# H01R0_Backend.net
KiCad netlist of a schematic drawn in Altium Designer
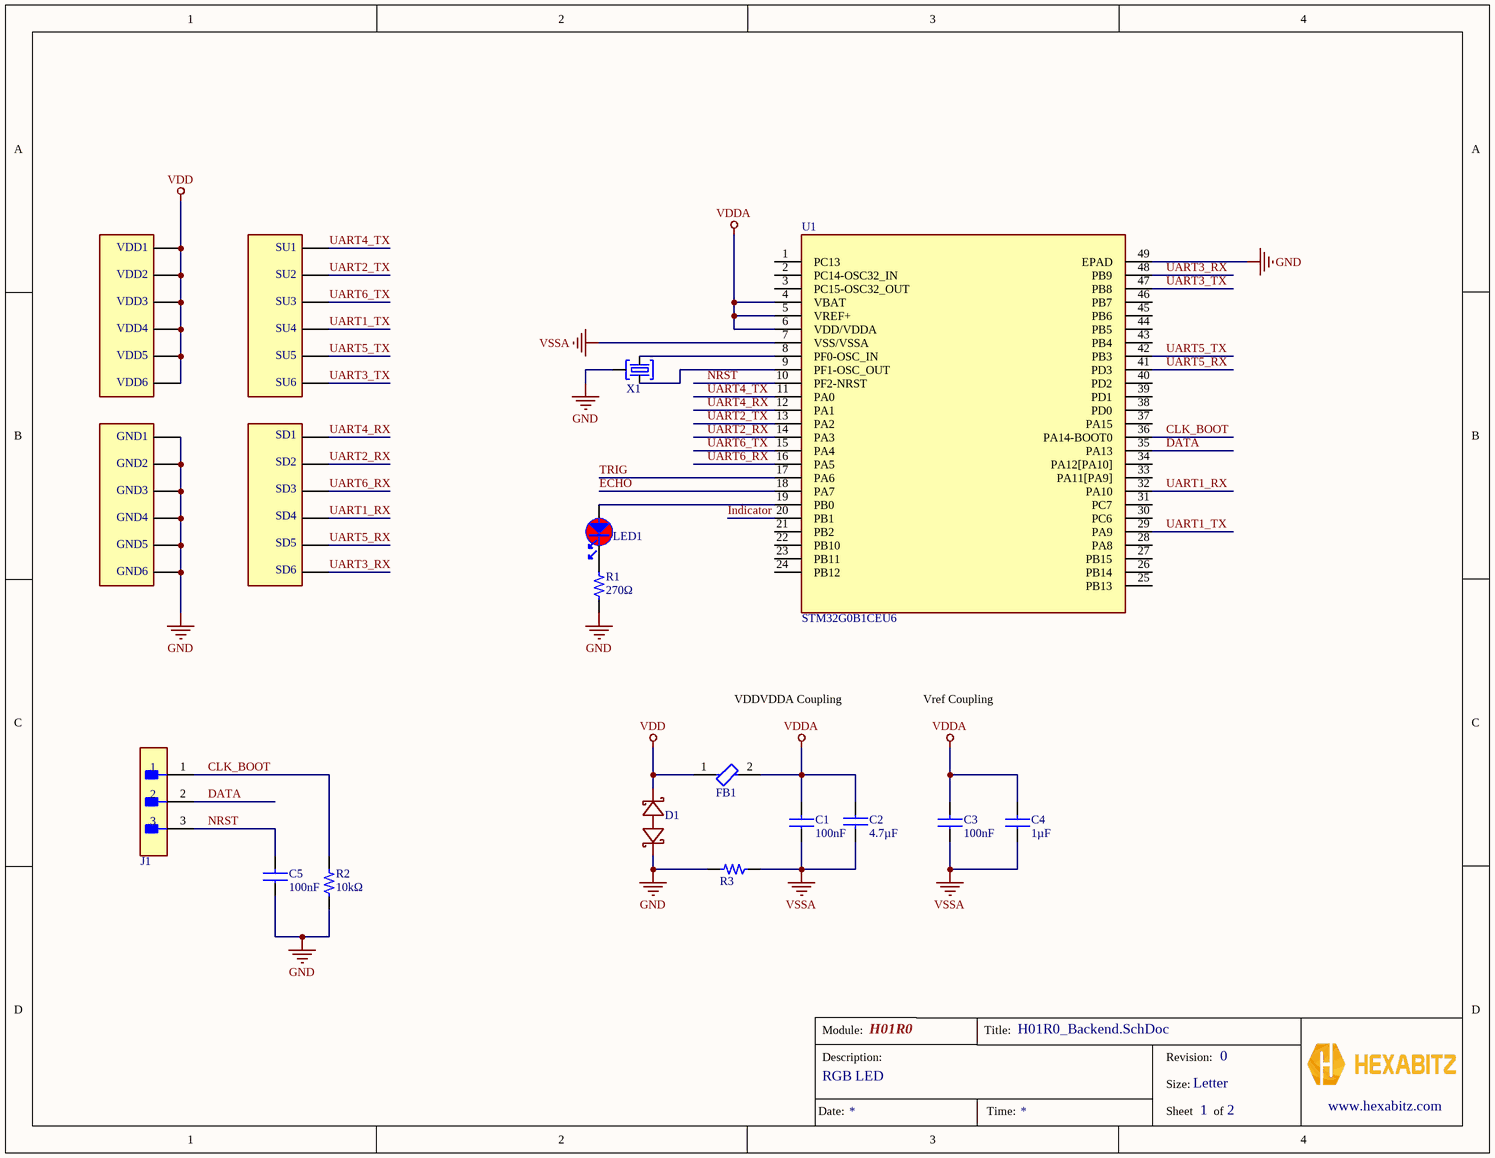
[diagram p0: H01R0_Backend.SchDoc]

(export (version "E")
  (design (tool "Eeschema 10.0.6"))
  (components
    (comp (ref "C1")
      (value "100nF")
      (footprint "C0603")
      (fields
        (field (name "MANUFACTURER") "Samsung Electro-Mechanics")
        (field (name "MANUFACTURER PART NUMBER") "CL10B104KA8NNNC")
        (field (name "TOLERANCE") "10%")
      )
      (libsource (lib "Hexabitz Altium Library") (part "generic Capacitor"))
    )
    (comp (ref "C2")
      (value "4.7µF")
      (footprint "C0805")
      (fields
        (field (name "MANUFACTURER") "Samsung Electro-Mechanics")
        (field (name "MANUFACTURER PART NUMBER") "CL21X475KAQNNNE")
        (field (name "TOLERANCE") "10%")
      )
      (libsource (lib "Hexabitz Altium Library") (part "generic Capacitor"))
    )
    (comp (ref "C3")
      (value "100nF")
      (footprint "C0603")
      (fields
        (field (name "MANUFACTURER") "Samsung Electro-Mechanics")
        (field (name "MANUFACTURER PART NUMBER") "CL10B104KA8NNNC")
        (field (name "TOLERANCE") "10%")
      )
      (libsource (lib "Hexabitz Altium Library") (part "generic Capacitor"))
    )
    (comp (ref "C4")
      (value "1µF")
      (footprint "C0805")
      (description "Ceramic Capacitor, Ceramic, 16V, 10% +Tol, 10% -Tol, X7R, 15% TC, 1uF, Surface Mount, 0805")
      (fields
        (field (name "MANUFACTURER") "Yageo Group")
        (field (name "MANUFACTURER PART NUMBER") "CC0805KKX7R7BB105")
      )
      (libsource (lib "Hexabitz Altium Library") (part "generic Capacitor"))
    )
    (comp (ref "C5")
      (value "100nF")
      (footprint "C0603")
      (fields
        (field (name "MANUFACTURER") "Samsung Electro-Mechanics")
        (field (name "MANUFACTURER PART NUMBER") "CL10B104KA8NNNC")
        (field (name "TOLERANCE") "10%")
      )
      (libsource (lib "Hexabitz Altium Library") (part "generic Capacitor"))
    )
    (comp (ref "D1")
      (value "CDSOD323-T03SC")
      (footprint "SOD2513X114N")
      (description "A 3V, 350W, bi-directional, standard capacitance, SOD323 pkg TVS Diode ¦ Bourns CDSOD323-T03SC")
      (fields (field (name "MANUFACTURER") "Bourns"))
      (libsource (lib "Hexabitz Altium Library") (part "CDSOD323-T03SC"))
    )
    (comp (ref "FB1")
      (value "MMZ1608Y300B")
      (footprint "FP-MMZ1608-0_8-MFG")
      (description "Ferrite Beads 0603 30ohms 1500mA Signal Line AEC-Q200")
      (fields
        (field (name "MANUFACTURER") "TDK")
        (field (name "MANUFACTURER PART NUMBER") "MMZ1608Y300BTD25")
      )
      (libsource (lib "Hexabitz Altium Library") (part "MMZ1608Y300B"))
    )
    (comp (ref "GND1")
      (value "HEXABIT_UART_PORT")
      (footprint "HEXABIT_POWER_PORT_D")
      (libsource (lib "hexabitz_connectors.Library") (part "HEXABIT_POWER_PORT_D"))
    )
    (comp (ref "GND2")
      (value "HEXABIT_UART_PORT")
      (footprint "HEXABIT_POWER_PORT_D")
      (libsource (lib "hexabitz_connectors.Library") (part "HEXABIT_POWER_PORT_D"))
    )
    (comp (ref "GND3")
      (value "HEXABIT_UART_PORT")
      (footprint "HEXABIT_POWER_PORT_D")
      (libsource (lib "hexabitz_connectors.Library") (part "HEXABIT_POWER_PORT_D"))
    )
    (comp (ref "GND4")
      (value "HEXABIT_UART_PORT")
      (footprint "HEXABIT_POWER_PORT_D")
      (libsource (lib "hexabitz_connectors.Library") (part "HEXABIT_POWER_PORT_D"))
    )
    (comp (ref "GND5")
      (value "HEXABIT_UART_PORT")
      (footprint "HEXABIT_POWER_PORT_D")
      (libsource (lib "hexabitz_connectors.Library") (part "HEXABIT_POWER_PORT_D"))
    )
    (comp (ref "GND6")
      (value "HEXABIT_UART_PORT")
      (footprint "HEXABIT_POWER_PORT_D")
      (libsource (lib "hexabitz_connectors.Library") (part "HEXABIT_POWER_PORT_D"))
    )
    (comp (ref "J1")
      (value "TSW-103-14-G-S")
      (footprint "FP-TSW-103-14-G-S-MFG")
      (description "CONN HEADER VERT 3POS 2.54MM")
      (libsource (lib "Altium Content Vault") (part "cd3439d6ef35ae5d9b27ec4fdd3e828"))
    )
    (comp (ref "LED1")
      (value "VLMS1300-GS08")
      (footprint "FP-6_541-5092_01-4-MFG")
      (description "LED Uni-Color Super Red 639nm 2-Pin Chip 0603(1608Metric) T/R")
      (fields (field (name "MANUFACTURER") "Vishay Semiconductors"))
      (libsource (lib "Hexabitz Altium Library") (part "VLMS1300-GS08"))
    )
    (comp (ref "R1")
      (value "270Ω")
      (footprint "R0603")
      (description "Res Thick Film 0603 270 Ohm 5% 0.1W(1/10W) ±200ppm/C Pad SMD Automotive T/R")
      (fields
        (field (name "MANUFACTURER") "Panasonic")
        (field (name "MANUFACTURER PART NUMBER") "ERJ-3GEYJ271V")
      )
      (libsource (lib "") (part "generic Resistor_2"))
    )
    (comp (ref "R2")
      (value "10kΩ")
      (footprint "R0603")
      (description "100mW Thick Film Resistors ±100ppm/℃ ±1% 10kΩ 0603 Chip Resistor - Surface Mount ROHS")
      (fields
        (field (name "MANUFACTURER") "Yageo Group")
        (field (name "MANUFACTURER PART NUMBER") "RC0603FR-0710KL")
      )
      (libsource (lib "") (part "generic Resistor_1"))
    )
    (comp (ref "R3")
      (value "Manufacturer Part Number")
      (footprint "R0603")
      (libsource (lib "Hexabitz Altium Library") (part "generic Resistor"))
    )
    (comp (ref "SD1")
      (value "HEXABIT_UART_PORT")
      (footprint "HEXABIT_UART_PORT_D")
      (libsource (lib "hexabitz_connectors.Library") (part "HEXABIT_UART_PORT_D"))
    )
    (comp (ref "SD2")
      (value "HEXABIT_UART_PORT")
      (footprint "HEXABIT_UART_PORT_D")
      (libsource (lib "hexabitz_connectors.Library") (part "HEXABIT_UART_PORT_D"))
    )
    (comp (ref "SD3")
      (value "HEXABIT_UART_PORT")
      (footprint "HEXABIT_UART_PORT_D")
      (libsource (lib "hexabitz_connectors.Library") (part "HEXABIT_UART_PORT_D"))
    )
    (comp (ref "SD4")
      (value "HEXABIT_UART_PORT")
      (footprint "HEXABIT_UART_PORT_D")
      (libsource (lib "hexabitz_connectors.Library") (part "HEXABIT_UART_PORT_D"))
    )
    (comp (ref "SD5")
      (value "HEXABIT_UART_PORT")
      (footprint "HEXABIT_UART_PORT_D")
      (libsource (lib "hexabitz_connectors.Library") (part "HEXABIT_UART_PORT_D"))
    )
    (comp (ref "SD6")
      (value "HEXABIT_UART_PORT")
      (footprint "HEXABIT_UART_PORT_D")
      (libsource (lib "hexabitz_connectors.Library") (part "HEXABIT_UART_PORT_D"))
    )
    (comp (ref "SU1")
      (value "HEXABIT_UART_PORT")
      (footprint "HEXABIT_UART_PORT_U")
      (libsource (lib "hexabitz_connectors.Library") (part "HEXABIT_UART_PORT_U"))
    )
    (comp (ref "SU2")
      (value "HEXABIT_UART_PORT")
      (footprint "HEXABIT_UART_PORT_U")
      (libsource (lib "hexabitz_connectors.Library") (part "HEXABIT_UART_PORT_U"))
    )
    (comp (ref "SU3")
      (value "HEXABIT_UART_PORT")
      (footprint "HEXABIT_UART_PORT_U")
      (libsource (lib "hexabitz_connectors.Library") (part "HEXABIT_UART_PORT_U"))
    )
    (comp (ref "SU4")
      (value "HEXABIT_UART_PORT")
      (footprint "HEXABIT_UART_PORT_U")
      (libsource (lib "hexabitz_connectors.Library") (part "HEXABIT_UART_PORT_U"))
    )
    (comp (ref "SU5")
      (value "HEXABIT_UART_PORT")
      (footprint "HEXABIT_UART_PORT_U")
      (libsource (lib "hexabitz_connectors.Library") (part "HEXABIT_UART_PORT_U"))
    )
    (comp (ref "SU6")
      (value "HEXABIT_UART_PORT")
      (footprint "HEXABIT_UART_PORT_U")
      (libsource (lib "hexabitz_connectors.Library") (part "HEXABIT_UART_PORT_U"))
    )
    (comp (ref "U1")
      (value "STM32G0B1CEU6")
      (footprint "QFN50P700X700X65-49N-D")
      (description "MCU 32-bit ARM Cortex M0+ RISC 512KB Flash 1.8V/2.5V/3.3V 48-Pin UFQFPN EP Tray")
      (fields
        (field (name "MANUFACTURER") "STMicroelectronics")
        (field (name "MANUFACTURER PART NUMBER") "STM32G0B1CEU6")
      )
      (libsource (lib "Hexabitz Altium Library") (part "STM32G0B1CEU6"))
    )
    (comp (ref "VDD1")
      (value "HEXABIT_UART_PORT")
      (footprint "HEXABIT_POWER_PORT_U")
      (libsource (lib "hexabitz_connectors.Library") (part "HEXABIT_POWER_PORT_U"))
    )
    (comp (ref "VDD2")
      (value "HEXABIT_UART_PORT")
      (footprint "HEXABIT_POWER_PORT_U")
      (libsource (lib "hexabitz_connectors.Library") (part "HEXABIT_POWER_PORT_U"))
    )
    (comp (ref "VDD3")
      (value "HEXABIT_UART_PORT")
      (footprint "HEXABIT_POWER_PORT_U")
      (libsource (lib "hexabitz_connectors.Library") (part "HEXABIT_POWER_PORT_U"))
    )
    (comp (ref "VDD4")
      (value "HEXABIT_UART_PORT")
      (footprint "HEXABIT_POWER_PORT_U")
      (libsource (lib "hexabitz_connectors.Library") (part "HEXABIT_POWER_PORT_U"))
    )
    (comp (ref "VDD5")
      (value "HEXABIT_UART_PORT")
      (footprint "HEXABIT_POWER_PORT_U")
      (libsource (lib "hexabitz_connectors.Library") (part "HEXABIT_POWER_PORT_U"))
    )
    (comp (ref "VDD6")
      (value "HEXABIT_UART_PORT")
      (footprint "HEXABIT_POWER_PORT_U")
      (libsource (lib "hexabitz_connectors.Library") (part "HEXABIT_POWER_PORT_U"))
    )
    (comp (ref "X1")
      (value "CSTCE8M00G52Z-R0")
      (footprint "XTALL_CSTCE8M00G52")
      (description "Ceramic Resonator 8MHz ±0.5% (Tol) ±0.2% (Stability) 10pF 40Ohm 3-Pin CSMD T/R")
      (fields (field (name "MANUFACTURER") "Murata") (field (name "TOLERANCE") "0.5%"))
      (libsource (lib "Hexabitz Altium Library") (part "CSTCE8M00G52Z-R0"))
    )
  )
  (nets
    (net (code "1") (name "/CLK_BOOT") (class "Default")
      (node (ref "J1") (pin "1") (pinfunction "1_1") (pintype "passive"))
      (node (ref "R2") (pin "1") (pinfunction "1_1") (pintype "passive"))
      (node (ref "U1") (pin "36") (pinfunction "PA14-BOOT0_36") (pintype "passive"))
    )
    (net (code "2") (name "/DATA") (class "Default")
      (node (ref "J1") (pin "2") (pinfunction "2_2") (pintype "passive"))
      (node (ref "U1") (pin "35") (pinfunction "PA13_35") (pintype "passive"))
    )
    (net (code "3") (name "/ECHO") (class "Default")
      (node (ref "U1") (pin "18") (pinfunction "PA7_18") (pintype "passive"))
    )
    (net (code "4") (name "/Indicator") (class "Default")
      (node (ref "U1") (pin "20") (pinfunction "PB1_20") (pintype "passive"))
    )
    (net (code "5") (name "/NRST") (class "Default")
      (node (ref "C5") (pin "2") (pinfunction "2_2") (pintype "passive"))
      (node (ref "J1") (pin "3") (pinfunction "3_3") (pintype "passive"))
      (node (ref "U1") (pin "10") (pinfunction "PF2-NRST_10") (pintype "passive"))
    )
    (net (code "6") (name "/TRIG") (class "Default")
      (node (ref "U1") (pin "17") (pinfunction "PA6_17") (pintype "passive"))
    )
    (net (code "7") (name "/UART1_RX") (class "Default")
      (node (ref "SD4") (pin "UART_D") (pinfunction "UART_D_UART_D") (pintype "passive"))
      (node (ref "U1") (pin "32") (pinfunction "PA10_32") (pintype "passive"))
    )
    (net (code "8") (name "/UART1_TX") (class "Default")
      (node (ref "SU4") (pin "UART_U") (pinfunction "UART_U_UART_U") (pintype "passive"))
      (node (ref "U1") (pin "29") (pinfunction "PA9_29") (pintype "passive"))
    )
    (net (code "9") (name "/UART2_RX") (class "Default")
      (node (ref "SD2") (pin "UART_D") (pinfunction "UART_D_UART_D") (pintype "passive"))
      (node (ref "U1") (pin "14") (pinfunction "PA3_14") (pintype "passive"))
    )
    (net (code "10") (name "/UART2_TX") (class "Default")
      (node (ref "SU2") (pin "UART_U") (pinfunction "UART_U_UART_U") (pintype "passive"))
      (node (ref "U1") (pin "13") (pinfunction "PA2_13") (pintype "passive"))
    )
    (net (code "11") (name "/UART3_RX") (class "Default")
      (node (ref "SD6") (pin "UART_D") (pinfunction "UART_D_UART_D") (pintype "passive"))
      (node (ref "U1") (pin "48") (pinfunction "PB9_48") (pintype "passive"))
    )
    (net (code "12") (name "/UART3_TX") (class "Default")
      (node (ref "SU6") (pin "UART_U") (pinfunction "UART_U_UART_U") (pintype "passive"))
      (node (ref "U1") (pin "47") (pinfunction "PB8_47") (pintype "passive"))
    )
    (net (code "13") (name "/UART4_RX") (class "Default")
      (node (ref "SD1") (pin "UART_D") (pinfunction "UART_D_UART_D") (pintype "passive"))
      (node (ref "U1") (pin "12") (pinfunction "PA1_12") (pintype "passive"))
    )
    (net (code "14") (name "/UART4_TX") (class "Default")
      (node (ref "SU1") (pin "UART_U") (pinfunction "UART_U_UART_U") (pintype "passive"))
      (node (ref "U1") (pin "11") (pinfunction "PA0_11") (pintype "passive"))
    )
    (net (code "15") (name "/UART5_RX") (class "Default")
      (node (ref "SD5") (pin "UART_D") (pinfunction "UART_D_UART_D") (pintype "passive"))
      (node (ref "U1") (pin "41") (pinfunction "PD3_41") (pintype "passive"))
    )
    (net (code "16") (name "/UART5_TX") (class "Default")
      (node (ref "SU5") (pin "UART_U") (pinfunction "UART_U_UART_U") (pintype "passive"))
      (node (ref "U1") (pin "42") (pinfunction "PB3_42") (pintype "passive"))
    )
    (net (code "17") (name "/UART6_RX") (class "Default")
      (node (ref "SD3") (pin "UART_D") (pinfunction "UART_D_UART_D") (pintype "passive"))
      (node (ref "U1") (pin "16") (pinfunction "PA5_16") (pintype "passive"))
    )
    (net (code "18") (name "/UART6_TX") (class "Default")
      (node (ref "SU3") (pin "UART_U") (pinfunction "UART_U_UART_U") (pintype "passive"))
      (node (ref "U1") (pin "15") (pinfunction "PA4_15") (pintype "passive"))
    )
    (net (code "19") (name "GND") (class "Default")
      (node (ref "C5") (pin "1") (pinfunction "1_1") (pintype "passive"))
      (node (ref "D1") (pin "1") (pinfunction "A_1") (pintype "passive"))
      (node (ref "GND1") (pin "Pwr_D") (pinfunction "Pwr_D_Pwr_D") (pintype "passive"))
      (node (ref "GND2") (pin "Pwr_D") (pinfunction "Pwr_D_Pwr_D") (pintype "passive"))
      (node (ref "GND3") (pin "Pwr_D") (pinfunction "Pwr_D_Pwr_D") (pintype "passive"))
      (node (ref "GND4") (pin "Pwr_D") (pinfunction "Pwr_D_Pwr_D") (pintype "passive"))
      (node (ref "GND5") (pin "Pwr_D") (pinfunction "Pwr_D_Pwr_D") (pintype "passive"))
      (node (ref "GND6") (pin "Pwr_D") (pinfunction "Pwr_D_Pwr_D") (pintype "passive"))
      (node (ref "R1") (pin "1") (pinfunction "1_1") (pintype "passive"))
      (node (ref "R2") (pin "2") (pinfunction "2_2") (pintype "passive"))
      (node (ref "R3") (pin "1") (pinfunction "1_1") (pintype "passive"))
      (node (ref "U1") (pin "49") (pinfunction "EPAD_49") (pintype "passive"))
      (node (ref "X1") (pin "P$2") (pinfunction "2_P$2") (pintype "passive"))
    )
    (net (code "20") (name "Net-(LED1-Pad1)") (class "Default")
      (node (ref "LED1") (pin "1") (pintype "passive"))
      (node (ref "R1") (pin "2") (pinfunction "2_2") (pintype "passive"))
    )
    (net (code "21") (name "Net-(U1-PB0)") (class "Default")
      (node (ref "LED1") (pin "2") (pintype "passive"))
      (node (ref "U1") (pin "19") (pinfunction "PB0_19") (pintype "passive"))
    )
    (net (code "22") (name "Net-(U1-PF0-OSC_IN)") (class "Default")
      (node (ref "U1") (pin "8") (pinfunction "PF0-OSC_IN_8") (pintype "passive"))
      (node (ref "X1") (pin "P$3") (pinfunction "3_P$3") (pintype "passive"))
    )
    (net (code "23") (name "Net-(U1-PF1-OSC_OUT)") (class "Default")
      (node (ref "U1") (pin "9") (pinfunction "PF1-OSC_OUT_9") (pintype "passive"))
      (node (ref "X1") (pin "P$1") (pinfunction "1_P$1") (pintype "passive"))
    )
    (net (code "24") (name "VDD") (class "Default")
      (node (ref "D1") (pin "2") (pinfunction "C_2") (pintype "passive"))
      (node (ref "FB1") (pin "1") (pinfunction "1_1") (pintype "passive"))
      (node (ref "VDD1") (pin "Pwr_U") (pinfunction "Pwr_U_Pwr_U") (pintype "passive"))
      (node (ref "VDD2") (pin "Pwr_U") (pinfunction "Pwr_U_Pwr_U") (pintype "passive"))
      (node (ref "VDD3") (pin "Pwr_U") (pinfunction "Pwr_U_Pwr_U") (pintype "passive"))
      (node (ref "VDD4") (pin "Pwr_U") (pinfunction "Pwr_U_Pwr_U") (pintype "passive"))
      (node (ref "VDD5") (pin "Pwr_U") (pinfunction "Pwr_U_Pwr_U") (pintype "passive"))
      (node (ref "VDD6") (pin "Pwr_U") (pinfunction "Pwr_U_Pwr_U") (pintype "passive"))
    )
    (net (code "25") (name "VDDA") (class "Default")
      (node (ref "C1") (pin "2") (pinfunction "2_2") (pintype "passive"))
      (node (ref "C2") (pin "1") (pinfunction "1_1") (pintype "passive"))
      (node (ref "C3") (pin "2") (pinfunction "2_2") (pintype "passive"))
      (node (ref "C4") (pin "2") (pinfunction "2_2") (pintype "passive"))
      (node (ref "FB1") (pin "2") (pinfunction "2_2") (pintype "passive"))
      (node (ref "U1") (pin "4") (pinfunction "VBAT_4") (pintype "passive"))
      (node (ref "U1") (pin "5") (pinfunction "VREF+_5") (pintype "passive"))
      (node (ref "U1") (pin "6") (pinfunction "VDD/VDDA_6") (pintype "passive"))
    )
    (net (code "26") (name "VSSA") (class "Default")
      (node (ref "C1") (pin "1") (pinfunction "1_1") (pintype "passive"))
      (node (ref "C2") (pin "2") (pinfunction "2_2") (pintype "passive"))
      (node (ref "C3") (pin "1") (pinfunction "1_1") (pintype "passive"))
      (node (ref "C4") (pin "1") (pinfunction "1_1") (pintype "passive"))
      (node (ref "R3") (pin "2") (pinfunction "2_2") (pintype "passive"))
      (node (ref "U1") (pin "7") (pinfunction "VSS/VSSA_7") (pintype "passive"))
    )
    (net (code "27") (name "unconnected-(U1-PA8-Pad28)") (class "Default")
      (node (ref "U1") (pin "28") (pinfunction "PA8_28") (pintype "passive"))
    )
    (net (code "28") (name "unconnected-(U1-PA11[PA9]-Pad33)") (class "Default")
      (node (ref "U1") (pin "33") (pinfunction "PA11[PA9]_33") (pintype "passive"))
    )
    (net (code "29") (name "unconnected-(U1-PA12[PA10]-Pad34)") (class "Default")
      (node (ref "U1") (pin "34") (pinfunction "PA12[PA10]_34") (pintype "passive"))
    )
    (net (code "30") (name "unconnected-(U1-PA15-Pad37)") (class "Default")
      (node (ref "U1") (pin "37") (pinfunction "PA15_37") (pintype "passive"))
    )
    (net (code "31") (name "unconnected-(U1-PB2-Pad21)") (class "Default")
      (node (ref "U1") (pin "21") (pinfunction "PB2_21") (pintype "passive"))
    )
    (net (code "32") (name "unconnected-(U1-PB4-Pad43)") (class "Default")
      (node (ref "U1") (pin "43") (pinfunction "PB4_43") (pintype "passive"))
    )
    (net (code "33") (name "unconnected-(U1-PB5-Pad44)") (class "Default")
      (node (ref "U1") (pin "44") (pinfunction "PB5_44") (pintype "passive"))
    )
    (net (code "34") (name "unconnected-(U1-PB6-Pad45)") (class "Default")
      (node (ref "U1") (pin "45") (pinfunction "PB6_45") (pintype "passive"))
    )
    (net (code "35") (name "unconnected-(U1-PB7-Pad46)") (class "Default")
      (node (ref "U1") (pin "46") (pinfunction "PB7_46") (pintype "passive"))
    )
    (net (code "36") (name "unconnected-(U1-PB10-Pad22)") (class "Default")
      (node (ref "U1") (pin "22") (pinfunction "PB10_22") (pintype "passive"))
    )
    (net (code "37") (name "unconnected-(U1-PB11-Pad23)") (class "Default")
      (node (ref "U1") (pin "23") (pinfunction "PB11_23") (pintype "passive"))
    )
    (net (code "38") (name "unconnected-(U1-PB12-Pad24)") (class "Default")
      (node (ref "U1") (pin "24") (pinfunction "PB12_24") (pintype "passive"))
    )
    (net (code "39") (name "unconnected-(U1-PB13-Pad25)") (class "Default")
      (node (ref "U1") (pin "25") (pinfunction "PB13_25") (pintype "passive"))
    )
    (net (code "40") (name "unconnected-(U1-PB14-Pad26)") (class "Default")
      (node (ref "U1") (pin "26") (pinfunction "PB14_26") (pintype "passive"))
    )
    (net (code "41") (name "unconnected-(U1-PB15-Pad27)") (class "Default")
      (node (ref "U1") (pin "27") (pinfunction "PB15_27") (pintype "passive"))
    )
    (net (code "42") (name "unconnected-(U1-PC6-Pad30)") (class "Default")
      (node (ref "U1") (pin "30") (pinfunction "PC6_30") (pintype "passive"))
    )
    (net (code "43") (name "unconnected-(U1-PC7-Pad31)") (class "Default")
      (node (ref "U1") (pin "31") (pinfunction "PC7_31") (pintype "passive"))
    )
    (net (code "44") (name "unconnected-(U1-PC13-Pad1)") (class "Default")
      (node (ref "U1") (pin "1") (pinfunction "PC13_1") (pintype "passive"))
    )
    (net (code "45") (name "unconnected-(U1-PC14-OSC32_IN-Pad2)") (class "Default")
      (node (ref "U1") (pin "2") (pinfunction "PC14-OSC32_IN_2") (pintype "passive"))
    )
    (net (code "46") (name "unconnected-(U1-PC15-OSC32_OUT-Pad3)") (class "Default")
      (node (ref "U1") (pin "3") (pinfunction "PC15-OSC32_OUT_3") (pintype "passive"))
    )
    (net (code "47") (name "unconnected-(U1-PD0-Pad38)") (class "Default")
      (node (ref "U1") (pin "38") (pinfunction "PD0_38") (pintype "passive"))
    )
    (net (code "48") (name "unconnected-(U1-PD1-Pad39)") (class "Default")
      (node (ref "U1") (pin "39") (pinfunction "PD1_39") (pintype "passive"))
    )
    (net (code "49") (name "unconnected-(U1-PD2-Pad40)") (class "Default")
      (node (ref "U1") (pin "40") (pinfunction "PD2_40") (pintype "passive"))
    )
  )
)
